# Flex_Sensor.net
KiCad netlist of a schematic drawn in Altium Designer
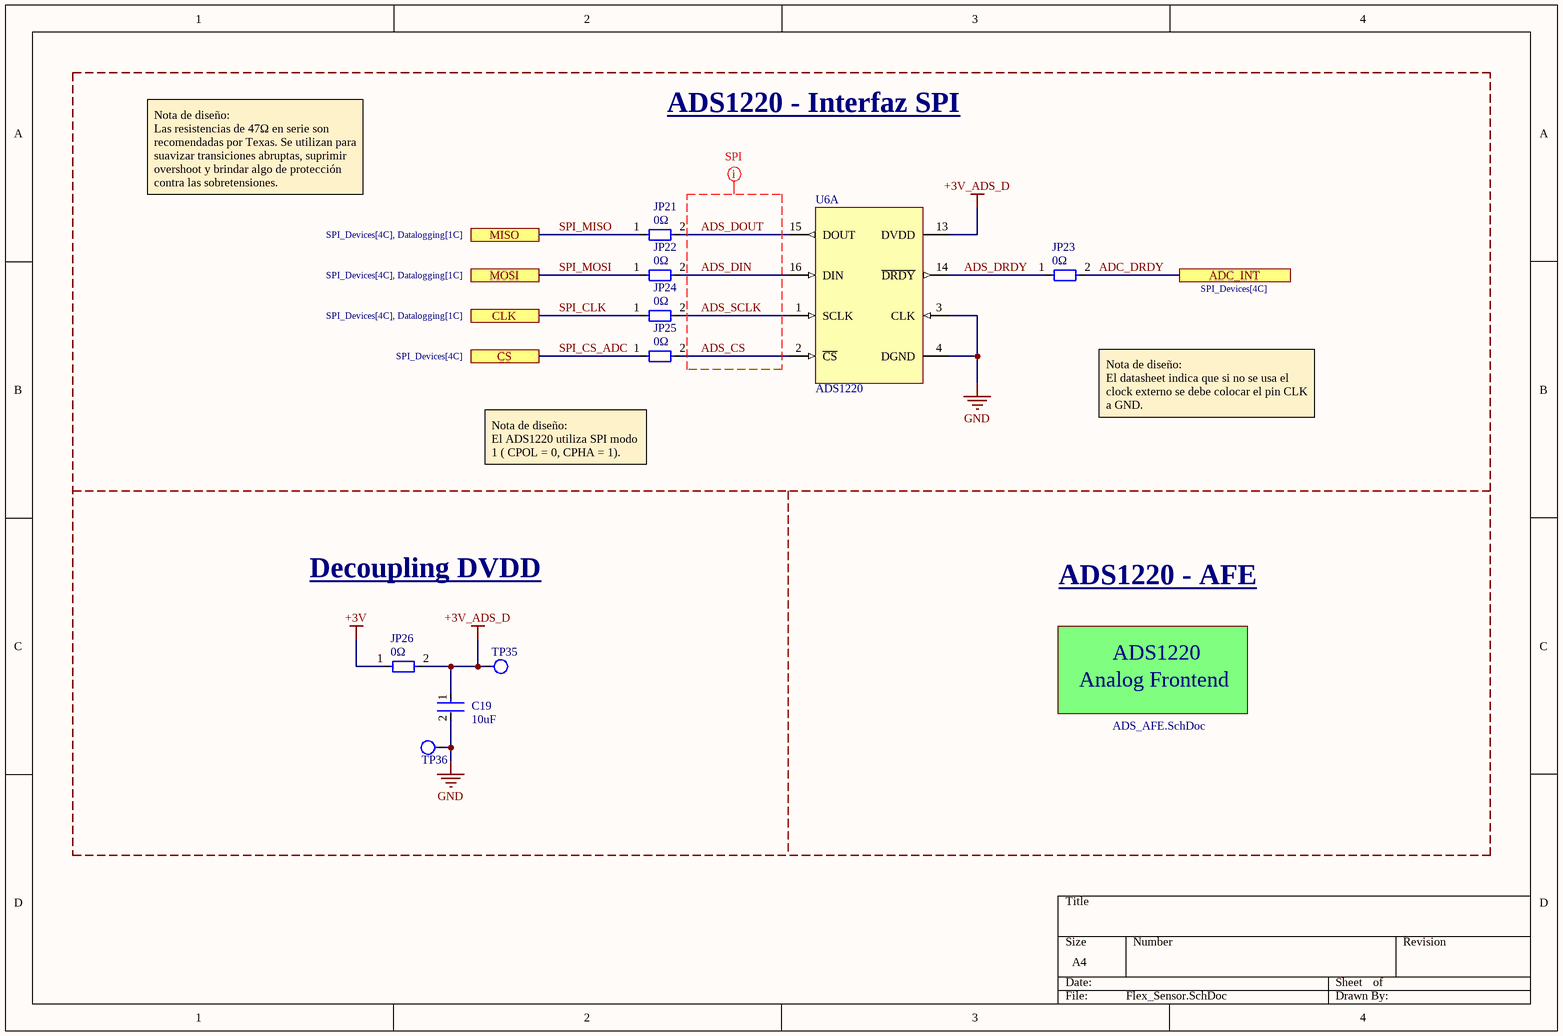
[diagram p0: Flex_Sensor.SchDoc]

(export (version "E")
  (design (tool "Eeschema 10.0.6"))
  (components
    (comp (ref "C19")
      (value "10uF")
      (footprint "CAP_0603")
      (description "Cap 10 uF 10V X7R 0603")
      (fields (field (name "CAPACITANCE") "10uF") (field (name "TOLERANCE") "10%"))
      (libsource (lib "Passive_Components") (part "Generic C"))
    )
    (comp (ref "JP21")
      (value "0Ω")
      (footprint "RES_0R_0603")
      (description "Simbolo de jumper genérico")
      (fields (field (name "Comment") "Generic JP"))
      (libsource (lib "Passive_Components") (part "Generic JP"))
    )
    (comp (ref "JP22")
      (value "0Ω")
      (footprint "RES_0R_0603")
      (description "Simbolo de jumper genérico")
      (fields (field (name "Comment") "Generic JP"))
      (libsource (lib "Passive_Components") (part "Generic JP"))
    )
    (comp (ref "JP23")
      (value "0Ω")
      (footprint "RES_0R_0603")
      (description "Simbolo de jumper genérico")
      (fields (field (name "Comment") "Generic JP"))
      (libsource (lib "Passive_Components") (part "Generic JP"))
    )
    (comp (ref "JP24")
      (value "0Ω")
      (footprint "RES_0R_0603")
      (description "Simbolo de jumper genérico")
      (fields (field (name "Comment") "Generic JP"))
      (libsource (lib "Passive_Components") (part "Generic JP"))
    )
    (comp (ref "JP25")
      (value "0Ω")
      (footprint "RES_0R_0603")
      (description "Simbolo de jumper genérico")
      (fields (field (name "Comment") "Generic JP"))
      (libsource (lib "Passive_Components") (part "Generic JP"))
    )
    (comp (ref "JP26")
      (value "0Ω")
      (footprint "RES_0R_0603")
      (description "Simbolo de jumper genérico")
      (fields (field (name "Comment") "Generic JP"))
      (libsource (lib "Passive_Components") (part "Generic JP"))
    )
    (comp (ref "TP35")
      (value "Testpoint SMD")
      (footprint "Testpoint_SMD")
      (description "Testpoint SMD de 1mm de diametro.")
      (libsource (lib "Connectors") (part "Testpoint_SMD"))
    )
    (comp (ref "TP36")
      (value "Testpoint SMD")
      (footprint "Testpoint_SMD")
      (description "Testpoint SMD de 1mm de diametro.")
      (libsource (lib "Connectors") (part "Testpoint_SMD"))
    )
    (comp (ref "U6")
      (value "ADS1220")
      (footprint "TSSOP-16")
      (description "ADS1220 4-Channel, 2-kSPS, Low-Power, 24-Bit ADC with Integrated PGA and Reference")
      (libsource (lib "ADC_DAC") (part "ADS1220"))
    )
  )
  (nets
    (net (code "1") (name "+3V") (class "Default")
      (node (ref "JP26") (pin "1") (pinfunction "1_1") (pintype "passive"))
    )
    (net (code "2") (name "+3V_ADS_D") (class "Default")
      (node (ref "C19") (pin "1") (pinfunction "1_1") (pintype "passive"))
      (node (ref "JP26") (pin "2") (pinfunction "2_2") (pintype "passive"))
      (node (ref "TP35") (pin "1") (pinfunction "1_1") (pintype "passive"))
      (node (ref "U6") (pin "13") (pinfunction "DVDD_13") (pintype "power_in"))
    )
    (net (code "3") (name "/ADC_DRDY") (class "Default")
      (node (ref "JP23") (pin "2") (pinfunction "2_2") (pintype "passive"))
    )
    (net (code "4") (name "/ADS_CS") (class "Default")
      (node (ref "JP25") (pin "2") (pinfunction "2_2") (pintype "passive"))
      (node (ref "U6") (pin "2") (pinfunction "CS_2") (pintype "input"))
    )
    (net (code "5") (name "/ADS_DIN") (class "Default")
      (node (ref "JP22") (pin "2") (pinfunction "2_2") (pintype "passive"))
      (node (ref "U6") (pin "16") (pinfunction "DIN_16") (pintype "input"))
    )
    (net (code "6") (name "/ADS_DOUT") (class "Default")
      (node (ref "JP21") (pin "2") (pinfunction "2_2") (pintype "passive"))
      (node (ref "U6") (pin "15") (pinfunction "DOUT_15") (pintype "output"))
    )
    (net (code "7") (name "/ADS_DRDY") (class "Default")
      (node (ref "JP23") (pin "1") (pinfunction "1_1") (pintype "passive"))
      (node (ref "U6") (pin "14") (pinfunction "DRDY_14") (pintype "output"))
    )
    (net (code "8") (name "/ADS_SCLK") (class "Default")
      (node (ref "JP24") (pin "2") (pinfunction "2_2") (pintype "passive"))
      (node (ref "U6") (pin "1") (pinfunction "SCLK_1") (pintype "input"))
    )
    (net (code "9") (name "/SPI_CLK") (class "Default")
      (node (ref "JP24") (pin "1") (pinfunction "1_1") (pintype "passive"))
    )
    (net (code "10") (name "/SPI_CS_ADC") (class "Default")
      (node (ref "JP25") (pin "1") (pinfunction "1_1") (pintype "passive"))
    )
    (net (code "11") (name "/SPI_MISO") (class "Default")
      (node (ref "JP21") (pin "1") (pinfunction "1_1") (pintype "passive"))
    )
    (net (code "12") (name "/SPI_MOSI") (class "Default")
      (node (ref "JP22") (pin "1") (pinfunction "1_1") (pintype "passive"))
    )
    (net (code "13") (name "GND") (class "Default")
      (node (ref "C19") (pin "2") (pinfunction "2_2") (pintype "passive"))
      (node (ref "TP36") (pin "1") (pinfunction "1_1") (pintype "passive"))
      (node (ref "U6") (pin "3") (pinfunction "CLK_3") (pintype "input"))
      (node (ref "U6") (pin "4") (pinfunction "DGND_4") (pintype "power_in"))
    )
  )
)
